# CanController.net
KiCad netlist of a schematic drawn in EAGLE
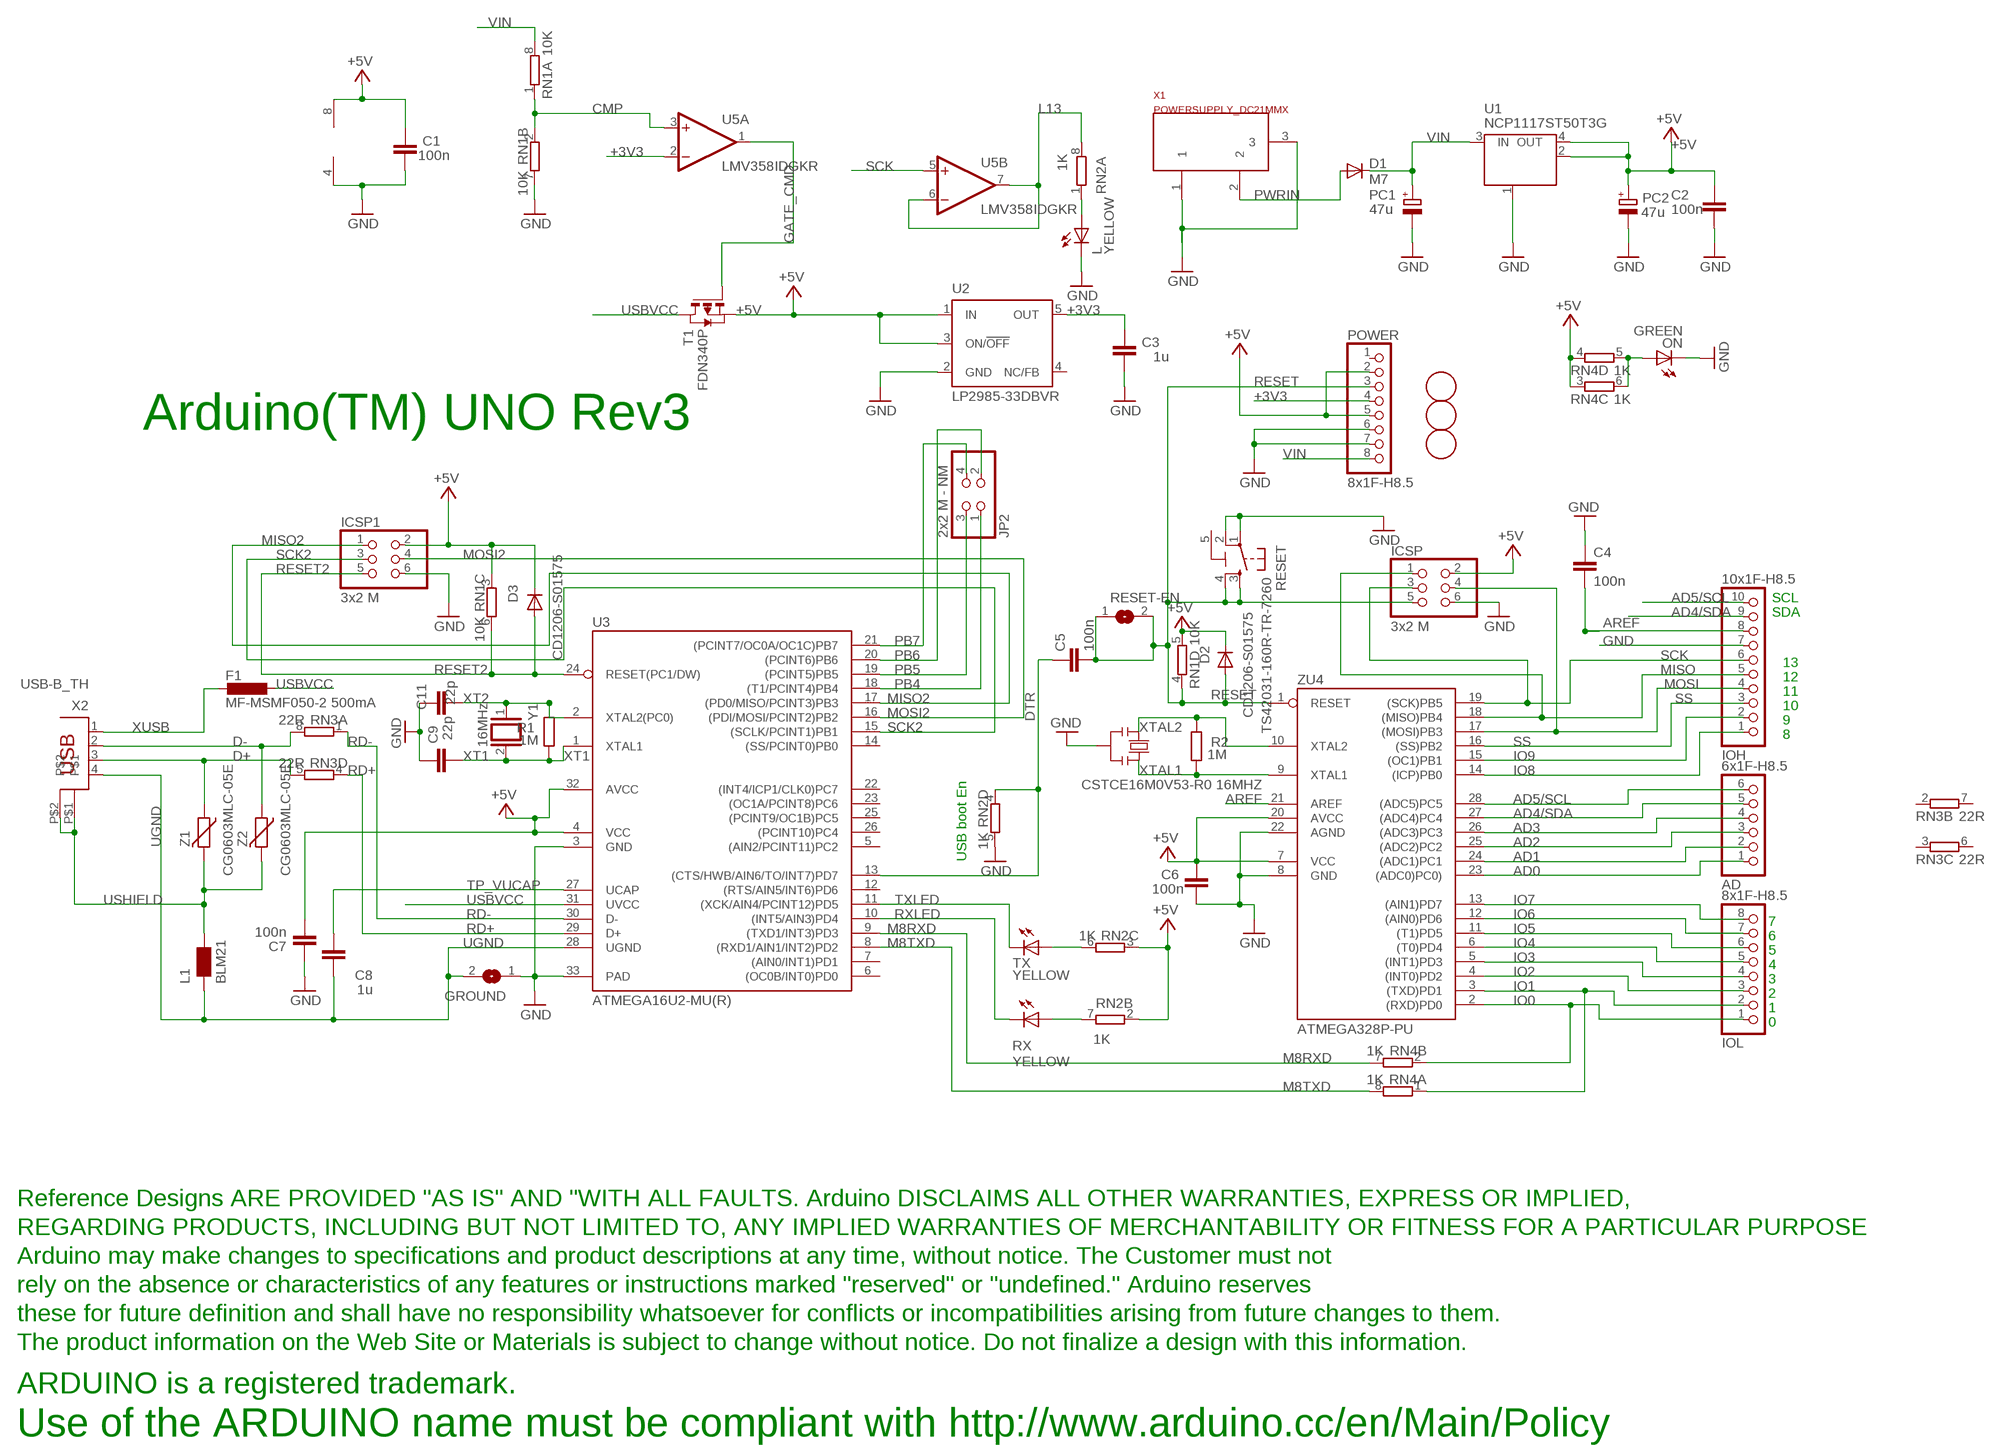
[diagram p0: schematic, sheet 2]

(export (version "E")
  (design (tool "Eeschema 10.0.6"))
  (components
    (comp (ref "AD")
      (value "6x1F-H8.5")
      (footprint "eagle-import:1X06")
      (libsource (lib "eagle-import") (part "PINHD-1X6"))
    )
    (comp (ref "C1")
      (value "100n")
      (footprint "eagle-import:C0603-ROUND")
      (libsource (lib "eagle-import") (part "C-EU0603-RND"))
    )
    (comp (ref "C2")
      (value "100n")
      (footprint "eagle-import:C0603-ROUND")
      (libsource (lib "eagle-import") (part "C-EU0603-RND"))
    )
    (comp (ref "C3")
      (value "1u")
      (footprint "eagle-import:C0603-ROUND")
      (libsource (lib "eagle-import") (part "C-EU0603-RND"))
    )
    (comp (ref "C4")
      (value "100n")
      (footprint "eagle-import:C0603-ROUND")
      (libsource (lib "eagle-import") (part "C-EU0603-RND"))
    )
    (comp (ref "C5")
      (value "100n")
      (footprint "eagle-import:C0603-ROUND")
      (libsource (lib "eagle-import") (part "C-EU0603-RND"))
    )
    (comp (ref "C6")
      (value "100n")
      (footprint "eagle-import:C0603-ROUND")
      (libsource (lib "eagle-import") (part "C-EU0603-RND"))
    )
    (comp (ref "C7")
      (value "100n")
      (footprint "eagle-import:C0603-ROUND")
      (libsource (lib "eagle-import") (part "C-EU0603-RND"))
    )
    (comp (ref "C8")
      (value "1u")
      (footprint "eagle-import:C0603-ROUND")
      (libsource (lib "eagle-import") (part "C-EU0603-RND"))
    )
    (comp (ref "C9")
      (value "22p")
      (footprint "eagle-import:C0603-ROUND")
      (libsource (lib "eagle-import") (part "C-EU0603-RND"))
    )
    (comp (ref "C11")
      (value "22p")
      (footprint "eagle-import:C0603-ROUND")
      (libsource (lib "eagle-import") (part "C-EU0603-RND"))
    )
    (comp (ref "D1")
      (value "M7")
      (footprint "eagle-import:SMB")
      (libsource (lib "eagle-import") (part "DIODE-SMB"))
    )
    (comp (ref "D2")
      (value "CD1206-S01575")
      (footprint "eagle-import:MINIMELF")
      (libsource (lib "eagle-import") (part "DIODE-MINIMELF"))
    )
    (comp (ref "D3")
      (value "CD1206-S01575")
      (footprint "eagle-import:MINIMELF")
      (libsource (lib "eagle-import") (part "DIODE-MINIMELF"))
    )
    (comp (ref "F1")
      (value "MF-MSMF050-2 500mA")
      (footprint "eagle-import:L1812")
      (libsource (lib "eagle-import") (part "L-EUL1812"))
    )
    (comp (ref "FD1")
      (value "FIDUCIALMOUNT")
      (footprint "eagle-import:FIDUCIA-MOUNT")
      (libsource (lib "eagle-import") (part "FIDUCIALMOUNT"))
    )
    (comp (ref "FD2")
      (value "FIDUCIALMOUNT")
      (footprint "eagle-import:FIDUCIA-MOUNT")
      (libsource (lib "eagle-import") (part "FIDUCIALMOUNT"))
    )
    (comp (ref "FD3")
      (value "FIDUCIALMOUNT")
      (footprint "eagle-import:FIDUCIA-MOUNT")
      (libsource (lib "eagle-import") (part "FIDUCIALMOUNT"))
    )
    (comp (ref "GROUND")
      (value "SJ")
      (footprint "eagle-import:SJ")
      (libsource (lib "eagle-import") (part "SJ"))
    )
    (comp (ref "ICSP")
      (value "3x2 M")
      (footprint "eagle-import:2X03")
      (libsource (lib "eagle-import") (part "PINHD-2X3"))
    )
    (comp (ref "ICSP1")
      (value "3x2 M")
      (footprint "eagle-import:2X03")
      (libsource (lib "eagle-import") (part "PINHD-2X3"))
    )
    (comp (ref "IOH")
      (value "10x1F-H8.5")
      (footprint "eagle-import:1X10")
      (libsource (lib "eagle-import") (part "PINHD-1X10_ARD"))
    )
    (comp (ref "IOL")
      (value "8x1F-H8.5")
      (footprint "eagle-import:1X08")
      (libsource (lib "eagle-import") (part "PINHD-1X8"))
    )
    (comp (ref "JP2")
      (value "2x2 M - NM")
      (footprint "eagle-import:2X02")
      (libsource (lib "eagle-import") (part "PINHD-2X2"))
    )
    (comp (ref "L")
      (value "YELLOW")
      (footprint "eagle-import:CHIP-LED0805")
      (libsource (lib "eagle-import") (part "LEDCHIP-LED0805"))
    )
    (comp (ref "L1")
      (value "BLM21")
      (footprint "eagle-import:0805")
      (libsource (lib "eagle-import") (part "WE-CBF_0805"))
    )
    (comp (ref "ON")
      (value "GREEN")
      (footprint "eagle-import:CHIP-LED0805")
      (libsource (lib "eagle-import") (part "LEDCHIP-LED0805"))
    )
    (comp (ref "PC1")
      (value "47u")
      (footprint "eagle-import:PANASONIC_D")
      (libsource (lib "eagle-import") (part "CPOL-EUD"))
    )
    (comp (ref "PC2")
      (value "47u")
      (footprint "eagle-import:PANASONIC_D")
      (libsource (lib "eagle-import") (part "CPOL-EUD"))
    )
    (comp (ref "POWER")
      (value "8x1F-H8.5")
      (footprint "eagle-import:1X08")
      (libsource (lib "eagle-import") (part "PINHD-1X8"))
    )
    (comp (ref "R1")
      (value "1M")
      (footprint "eagle-import:R0603-ROUND")
      (libsource (lib "eagle-import") (part "R-EU_R0603"))
    )
    (comp (ref "R2")
      (value "1M")
      (footprint "eagle-import:R0603-ROUND")
      (libsource (lib "eagle-import") (part "R-EU_R0603"))
    )
    (comp (ref "RESET")
      (value "TS42031-160R-TR-7260")
      (footprint "eagle-import:TS42")
      (libsource (lib "eagle-import") (part "TS42"))
    )
    (comp (ref "RESET-EN")
      (value "SJ")
      (footprint "eagle-import:SJ")
      (libsource (lib "eagle-import") (part "SJ"))
    )
    (comp (ref "RN1")
      (value "10K")
      (footprint "eagle-import:CAY16")
      (libsource (lib "eagle-import") (part "4R-NCAY16"))
    )
    (comp (ref "RN2")
      (value "1K")
      (footprint "eagle-import:CAY16")
      (libsource (lib "eagle-import") (part "4R-NCAY16"))
    )
    (comp (ref "RN3")
      (value "22R")
      (footprint "eagle-import:CAY16")
      (libsource (lib "eagle-import") (part "4R-NCAY16"))
    )
    (comp (ref "RN4")
      (value "1K")
      (footprint "eagle-import:CAY16")
      (libsource (lib "eagle-import") (part "4R-NCAY16"))
    )
    (comp (ref "RX")
      (value "YELLOW")
      (footprint "eagle-import:CHIP-LED0805")
      (libsource (lib "eagle-import") (part "LEDCHIP-LED0805"))
    )
    (comp (ref "T1")
      (value "FDN340P")
      (footprint "eagle-import:SOT-23")
      (libsource (lib "eagle-import") (part "PMOSSOT23"))
    )
    (comp (ref "TX")
      (value "YELLOW")
      (footprint "eagle-import:CHIP-LED0805")
      (libsource (lib "eagle-import") (part "LEDCHIP-LED0805"))
    )
    (comp (ref "U$1")
      (value "DISCLAIMER")
      (footprint "eagle-import:DISCLAIMER")
      (libsource (lib "eagle-import") (part "DISCLAIMER"))
    )
    (comp (ref "U1")
      (value "NCP1117ST50T3G")
      (footprint "eagle-import:SOT223")
      (libsource (lib "eagle-import") (part "MC33269ST-3.3T3"))
    )
    (comp (ref "U2")
      (value "LP2985-33DBVR")
      (footprint "eagle-import:SOT23-DBV")
      (libsource (lib "eagle-import") (part "LP2985-XXDBVR33"))
    )
    (comp (ref "U3")
      (value "ATMEGA16U2-MU(R)")
      (footprint "eagle-import:MLF32")
      (libsource (lib "eagle-import") (part "ATMEGA16U2-MU"))
    )
    (comp (ref "U5")
      (value "LMV358IDGKR")
      (footprint "eagle-import:MSOP08")
      (libsource (lib "eagle-import") (part "LMV358?MMX"))
    )
    (comp (ref "X1")
      (value "POWERSUPPLY_DC21MMX")
      (footprint "eagle-import:POWERSUPPLY_DC-21MM")
      (libsource (lib "eagle-import") (part "POWERSUPPLY_DC21MMX"))
    )
    (comp (ref "X2")
      (value "USB-B_TH")
      (footprint "eagle-import:PN61729")
      (libsource (lib "eagle-import") (part "PN61729"))
    )
    (comp (ref "Y1")
      (value "16MHz")
      (footprint "eagle-import:QS")
      (libsource (lib "eagle-import") (part "XTAL/S"))
    )
    (comp (ref "Y2")
      (value "CSTCE16M0V53-R0 16MHZ")
      (footprint "eagle-import:RESONATOR")
      (libsource (lib "eagle-import") (part "RESONATORMU"))
    )
    (comp (ref "Z1")
      (value "CG0603MLC-05E")
      (footprint "eagle-import:CT_CN0603")
      (libsource (lib "eagle-import") (part "VARISTORCN0603"))
    )
    (comp (ref "Z2")
      (value "CG0603MLC-05E")
      (footprint "eagle-import:CT_CN0603")
      (libsource (lib "eagle-import") (part "VARISTORCN0603"))
    )
    (comp (ref "ZU4")
      (value "ATMEGA328P-PU")
      (footprint "eagle-import:DIL28-3")
      (libsource (lib "eagle-import") (part "ATMEGA328P-PU"))
    )
  )
  (nets
    (net (code "1") (name "+3V3") (class "Default")
      (node (ref "C3") (pin "2") (pinfunction "2_2") (pintype "passive"))
      (node (ref "POWER") (pin "4") (pinfunction "4_4") (pintype "passive"))
      (node (ref "U2") (pin "5") (pinfunction "OUT_5") (pintype "passive"))
      (node (ref "U5") (pin "2") (pinfunction "-IN_2") (pintype "input"))
    )
    (net (code "2") (name "+5V") (class "Default")
      (node (ref "C1") (pin "2") (pinfunction "2_2") (pintype "passive"))
      (node (ref "C2") (pin "2") (pinfunction "2_2") (pintype "passive"))
      (node (ref "C6") (pin "2") (pinfunction "2_2") (pintype "passive"))
      (node (ref "C7") (pin "1") (pinfunction "1_1") (pintype "passive"))
      (node (ref "D2") (pin "C") (pinfunction "C_C") (pintype "passive"))
      (node (ref "D3") (pin "C") (pinfunction "C_C") (pintype "passive"))
      (node (ref "ICSP") (pin "2") (pinfunction "2_2") (pintype "passive"))
      (node (ref "ICSP1") (pin "2") (pinfunction "2_2") (pintype "passive"))
      (node (ref "PC2") (pin "+") (pinfunction "+_+") (pintype "passive"))
      (node (ref "POWER") (pin "2") (pinfunction "2_2") (pintype "passive"))
      (node (ref "POWER") (pin "5") (pinfunction "5_5") (pintype "passive"))
      (node (ref "RN1") (pin "3") (pinfunction "1_3") (pintype "passive"))
      (node (ref "RN1") (pin "5") (pinfunction "2_5") (pintype "passive"))
      (node (ref "RN2") (pin "2") (pinfunction "1_2") (pintype "passive"))
      (node (ref "RN2") (pin "3") (pinfunction "1_3") (pintype "passive"))
      (node (ref "RN4") (pin "3") (pinfunction "1_3") (pintype "passive"))
      (node (ref "RN4") (pin "4") (pinfunction "1_4") (pintype "passive"))
      (node (ref "T1") (pin "2") (pinfunction "S_2") (pintype "passive"))
      (node (ref "U1") (pin "2") (pinfunction "OUT_2") (pintype "passive"))
      (node (ref "U1") (pin "4") (pinfunction "OUT_4") (pintype "passive"))
      (node (ref "U2") (pin "1") (pinfunction "IN_1") (pintype "input"))
      (node (ref "U2") (pin "3") (pinfunction "ON/~{OFF}_3") (pintype "input"))
      (node (ref "U3") (pin "32") (pinfunction "AVCC_32") (pintype "power_in"))
      (node (ref "U3") (pin "4") (pinfunction "VCC_4") (pintype "power_in"))
      (node (ref "U5") (pin "8") (pinfunction "V+_8") (pintype "power_in"))
      (node (ref "ZU4") (pin "20") (pinfunction "AVCC_20") (pintype "power_in"))
      (node (ref "ZU4") (pin "7") (pinfunction "VCC_7") (pintype "power_in"))
    )
    (net (code "3") (name "5-GND") (class "Default")
      (node (ref "RESET") (pin "5") (pinfunction "5-GND_5") (pintype "power_in"))
    )
    (net (code "4") (name "AD0") (class "Default")
      (node (ref "AD") (pin "1") (pinfunction "1_1") (pintype "passive"))
      (node (ref "ZU4") (pin "23") (pinfunction "(ADC0)PC0)_23") (pintype "bidirectional"))
    )
    (net (code "5") (name "AD1") (class "Default")
      (node (ref "AD") (pin "2") (pinfunction "2_2") (pintype "passive"))
      (node (ref "ZU4") (pin "24") (pinfunction "(ADC1)PC1_24") (pintype "bidirectional"))
    )
    (net (code "6") (name "AD2") (class "Default")
      (node (ref "AD") (pin "3") (pinfunction "3_3") (pintype "passive"))
      (node (ref "ZU4") (pin "25") (pinfunction "(ADC2)PC2_25") (pintype "bidirectional"))
    )
    (net (code "7") (name "AD3") (class "Default")
      (node (ref "AD") (pin "4") (pinfunction "4_4") (pintype "passive"))
      (node (ref "ZU4") (pin "26") (pinfunction "(ADC3)PC3_26") (pintype "bidirectional"))
    )
    (net (code "8") (name "AD4{slash}SDA") (class "Default")
      (node (ref "AD") (pin "5") (pinfunction "5_5") (pintype "passive"))
      (node (ref "IOH") (pin "9") (pinfunction "9_9") (pintype "passive"))
      (node (ref "ZU4") (pin "27") (pinfunction "(ADC4)PC4_27") (pintype "bidirectional"))
    )
    (net (code "9") (name "AD5{slash}SCL") (class "Default")
      (node (ref "AD") (pin "6") (pinfunction "6_6") (pintype "passive"))
      (node (ref "IOH") (pin "10") (pinfunction "10_10") (pintype "passive"))
      (node (ref "ZU4") (pin "28") (pinfunction "(ADC5)PC5_28") (pintype "bidirectional"))
    )
    (net (code "10") (name "AREF") (class "Default")
      (node (ref "C4") (pin "2") (pinfunction "2_2") (pintype "passive"))
      (node (ref "IOH") (pin "8") (pinfunction "8_8") (pintype "passive"))
      (node (ref "ZU4") (pin "21") (pinfunction "AREF_21") (pintype "passive"))
    )
    (net (code "11") (name "CMP") (class "Default")
      (node (ref "RN1") (pin "1") (pinfunction "1_1") (pintype "passive"))
      (node (ref "RN1") (pin "2") (pinfunction "1_2") (pintype "passive"))
      (node (ref "U5") (pin "3") (pinfunction "+IN_3") (pintype "input"))
    )
    (net (code "12") (name "D+") (class "Default")
      (node (ref "RN3") (pin "5") (pinfunction "2_5") (pintype "passive"))
      (node (ref "X2") (pin "3") (pinfunction "3_3") (pintype "bidirectional"))
      (node (ref "Z1") (pin "1") (pinfunction "1_1") (pintype "passive"))
    )
    (net (code "13") (name "D-") (class "Default")
      (node (ref "RN3") (pin "8") (pinfunction "2_8") (pintype "passive"))
      (node (ref "X2") (pin "2") (pinfunction "2_2") (pintype "bidirectional"))
      (node (ref "Z2") (pin "1") (pinfunction "1_1") (pintype "passive"))
    )
    (net (code "14") (name "DTR") (class "Default")
      (node (ref "C5") (pin "1") (pinfunction "1_1") (pintype "passive"))
      (node (ref "RN2") (pin "4") (pinfunction "1_4") (pintype "passive"))
      (node (ref "U3") (pin "13") (pinfunction "(CTS/HWB/AIN6/TO/INT7)PD7_13") (pintype "bidirectional"))
    )
    (net (code "15") (name "GATE_CMD") (class "Default")
      (node (ref "T1") (pin "3") (pinfunction "G_3") (pintype "passive"))
      (node (ref "U5") (pin "1") (pinfunction "OUT_1") (pintype "output"))
    )
    (net (code "16") (name "GND") (class "Default")
      (node (ref "C1") (pin "1") (pinfunction "1_1") (pintype "passive"))
      (node (ref "C11") (pin "2") (pinfunction "2_2") (pintype "passive"))
      (node (ref "C2") (pin "1") (pinfunction "1_1") (pintype "passive"))
      (node (ref "C3") (pin "1") (pinfunction "1_1") (pintype "passive"))
      (node (ref "C4") (pin "1") (pinfunction "1_1") (pintype "passive"))
      (node (ref "C6") (pin "1") (pinfunction "1_1") (pintype "passive"))
      (node (ref "C7") (pin "2") (pinfunction "2_2") (pintype "passive"))
      (node (ref "C9") (pin "2") (pinfunction "2_2") (pintype "passive"))
      (node (ref "GROUND") (pin "1") (pinfunction "1_1") (pintype "passive"))
      (node (ref "ICSP") (pin "6") (pinfunction "6_6") (pintype "passive"))
      (node (ref "ICSP1") (pin "6") (pinfunction "6_6") (pintype "passive"))
      (node (ref "IOH") (pin "7") (pinfunction "7_7") (pintype "passive"))
      (node (ref "L") (pin "C") (pinfunction "C_C") (pintype "passive"))
      (node (ref "ON") (pin "C") (pinfunction "C_C") (pintype "passive"))
      (node (ref "PC1") (pin "-") (pinfunction "-_-") (pintype "passive"))
      (node (ref "PC2") (pin "-") (pinfunction "-_-") (pintype "passive"))
      (node (ref "POWER") (pin "6") (pinfunction "6_6") (pintype "passive"))
      (node (ref "POWER") (pin "7") (pinfunction "7_7") (pintype "passive"))
      (node (ref "RESET") (pin "1") (pinfunction "1_1") (pintype "passive"))
      (node (ref "RESET") (pin "2") (pinfunction "2_2") (pintype "passive"))
      (node (ref "RN1") (pin "7") (pinfunction "2_7") (pintype "passive"))
      (node (ref "RN2") (pin "5") (pinfunction "2_5") (pintype "passive"))
      (node (ref "U1") (pin "1") (pinfunction "GND/ADJ_1") (pintype "input"))
      (node (ref "U2") (pin "2") (pinfunction "GND_2") (pintype "power_in"))
      (node (ref "U3") (pin "3") (pinfunction "GND_3") (pintype "power_in"))
      (node (ref "U3") (pin "33") (pinfunction "PAD_33") (pintype "power_in"))
      (node (ref "U5") (pin "4") (pinfunction "V-_4") (pintype "power_in"))
      (node (ref "X1") (pin "1") (pinfunction "1_1") (pintype "power_in"))
      (node (ref "X1") (pin "3") (pinfunction "3_3") (pintype "power_in"))
      (node (ref "Y2") (pin "2") (pinfunction "2_2") (pintype "passive"))
      (node (ref "ZU4") (pin "22") (pinfunction "AGND_22") (pintype "power_in"))
      (node (ref "ZU4") (pin "8") (pinfunction "GND_8") (pintype "power_in"))
    )
    (net (code "17") (name "IO0") (class "Default")
      (node (ref "IOL") (pin "1") (pinfunction "1_1") (pintype "passive"))
      (node (ref "RN4") (pin "2") (pinfunction "1_2") (pintype "passive"))
      (node (ref "ZU4") (pin "2") (pinfunction "(RXD)PD0_2") (pintype "bidirectional"))
    )
    (net (code "18") (name "IO1") (class "Default")
      (node (ref "IOL") (pin "2") (pinfunction "2_2") (pintype "passive"))
      (node (ref "RN4") (pin "1") (pinfunction "1_1") (pintype "passive"))
      (node (ref "ZU4") (pin "3") (pinfunction "(TXD)PD1_3") (pintype "bidirectional"))
    )
    (net (code "19") (name "IO2") (class "Default")
      (node (ref "IOL") (pin "3") (pinfunction "3_3") (pintype "passive"))
      (node (ref "ZU4") (pin "4") (pinfunction "(INT0)PD2_4") (pintype "bidirectional"))
    )
    (net (code "20") (name "IO3") (class "Default")
      (node (ref "IOL") (pin "4") (pinfunction "4_4") (pintype "passive"))
      (node (ref "ZU4") (pin "5") (pinfunction "(INT1)PD3_5") (pintype "bidirectional"))
    )
    (net (code "21") (name "IO4") (class "Default")
      (node (ref "IOL") (pin "5") (pinfunction "5_5") (pintype "passive"))
      (node (ref "ZU4") (pin "6") (pinfunction "(T0)PD4_6") (pintype "bidirectional"))
    )
    (net (code "22") (name "IO5") (class "Default")
      (node (ref "IOL") (pin "6") (pinfunction "6_6") (pintype "passive"))
      (node (ref "ZU4") (pin "11") (pinfunction "(T1)PD5_11") (pintype "bidirectional"))
    )
    (net (code "23") (name "IO6") (class "Default")
      (node (ref "IOL") (pin "7") (pinfunction "7_7") (pintype "passive"))
      (node (ref "ZU4") (pin "12") (pinfunction "(AIN0)PD6_12") (pintype "bidirectional"))
    )
    (net (code "24") (name "IO7") (class "Default")
      (node (ref "IOL") (pin "8") (pinfunction "8_8") (pintype "passive"))
      (node (ref "ZU4") (pin "13") (pinfunction "(AIN1)PD7_13") (pintype "bidirectional"))
    )
    (net (code "25") (name "IO8") (class "Default")
      (node (ref "IOH") (pin "1") (pinfunction "1_1") (pintype "passive"))
      (node (ref "ZU4") (pin "14") (pinfunction "(ICP)PB0_14") (pintype "bidirectional"))
    )
    (net (code "26") (name "IO9") (class "Default")
      (node (ref "IOH") (pin "2") (pinfunction "2_2") (pintype "passive"))
      (node (ref "ZU4") (pin "15") (pinfunction "(OC1)PB1_15") (pintype "bidirectional"))
    )
    (net (code "27") (name "L13") (class "Default")
      (node (ref "RN2") (pin "8") (pinfunction "2_8") (pintype "passive"))
      (node (ref "U5") (pin "6") (pinfunction "-IN_6") (pintype "input"))
      (node (ref "U5") (pin "7") (pinfunction "OUT_7") (pintype "output"))
    )
    (net (code "28") (name "M8RXD") (class "Default")
      (node (ref "RN4") (pin "7") (pinfunction "2_7") (pintype "passive"))
      (node (ref "U3") (pin "9") (pinfunction "(TXD1/INT3)PD3_9") (pintype "bidirectional"))
    )
    (net (code "29") (name "M8TXD") (class "Default")
      (node (ref "RN4") (pin "8") (pinfunction "2_8") (pintype "passive"))
      (node (ref "U3") (pin "8") (pinfunction "(RXD1/AIN1/INT2)PD2_8") (pintype "bidirectional"))
    )
    (net (code "30") (name "MISO") (class "Default")
      (node (ref "ICSP") (pin "1") (pinfunction "1_1") (pintype "passive"))
      (node (ref "IOH") (pin "5") (pinfunction "5_5") (pintype "passive"))
      (node (ref "ZU4") (pin "18") (pinfunction "(MISO)PB4_18") (pintype "bidirectional"))
    )
    (net (code "31") (name "MISO2") (class "Default")
      (node (ref "ICSP1") (pin "1") (pinfunction "1_1") (pintype "passive"))
      (node (ref "U3") (pin "17") (pinfunction "(PD0/MISO/PCINT3)PB3_17") (pintype "bidirectional"))
    )
    (net (code "32") (name "MOSI") (class "Default")
      (node (ref "ICSP") (pin "4") (pinfunction "4_4") (pintype "passive"))
      (node (ref "IOH") (pin "4") (pinfunction "4_4") (pintype "passive"))
      (node (ref "ZU4") (pin "17") (pinfunction "(MOSI)PB3_17") (pintype "bidirectional"))
    )
    (net (code "33") (name "MOSI2") (class "Default")
      (node (ref "ICSP1") (pin "4") (pinfunction "4_4") (pintype "passive"))
      (node (ref "U3") (pin "16") (pinfunction "(PDI/MOSI/PCINT2)PB2_16") (pintype "bidirectional"))
    )
    (net (code "34") (name "Net-(L-PadA)") (class "Default")
      (node (ref "L") (pin "A") (pinfunction "A_A") (pintype "passive"))
      (node (ref "RN2") (pin "1") (pinfunction "1_1") (pintype "passive"))
    )
    (net (code "35") (name "Net-(RN2B-2)") (class "Default")
      (node (ref "RN2") (pin "7") (pinfunction "2_7") (pintype "passive"))
      (node (ref "RX") (pin "A") (pinfunction "A_A") (pintype "passive"))
    )
    (net (code "36") (name "Net-(RN2C-2)") (class "Default")
      (node (ref "RN2") (pin "6") (pinfunction "2_6") (pintype "passive"))
      (node (ref "TX") (pin "A") (pinfunction "A_A") (pintype "passive"))
    )
    (net (code "37") (name "Net-(RN4C-2)") (class "Default")
      (node (ref "ON") (pin "A") (pinfunction "A_A") (pintype "passive"))
      (node (ref "RN4") (pin "5") (pinfunction "2_5") (pintype "passive"))
      (node (ref "RN4") (pin "6") (pinfunction "2_6") (pintype "passive"))
    )
    (net (code "38") (name "PB4") (class "Default")
      (node (ref "JP2") (pin "1") (pinfunction "1_1") (pintype "passive"))
      (node (ref "U3") (pin "18") (pinfunction "(T1/PCINT4)PB4_18") (pintype "bidirectional"))
    )
    (net (code "39") (name "PB5") (class "Default")
      (node (ref "JP2") (pin "3") (pinfunction "3_3") (pintype "passive"))
      (node (ref "U3") (pin "19") (pinfunction "(PCINT5)PB5_19") (pintype "bidirectional"))
    )
    (net (code "40") (name "PB6") (class "Default")
      (node (ref "JP2") (pin "2") (pinfunction "2_2") (pintype "passive"))
      (node (ref "U3") (pin "20") (pinfunction "(PCINT6)PB6_20") (pintype "bidirectional"))
    )
    (net (code "41") (name "PB7") (class "Default")
      (node (ref "JP2") (pin "4") (pinfunction "4_4") (pintype "passive"))
      (node (ref "U3") (pin "21") (pinfunction "(PCINT7/OC0A/OC1C)PB7_21") (pintype "bidirectional"))
    )
    (net (code "42") (name "PWRIN") (class "Default")
      (node (ref "D1") (pin "A") (pinfunction "A_A") (pintype "passive"))
      (node (ref "X1") (pin "2") (pinfunction "2_2") (pintype "power_in"))
    )
    (net (code "43") (name "RD+") (class "Default")
      (node (ref "RN3") (pin "4") (pinfunction "1_4") (pintype "passive"))
      (node (ref "U3") (pin "29") (pinfunction "D+_29") (pintype "bidirectional"))
    )
    (net (code "44") (name "RD-") (class "Default")
      (node (ref "RN3") (pin "1") (pinfunction "1_1") (pintype "passive"))
      (node (ref "U3") (pin "30") (pinfunction "D-_30") (pintype "bidirectional"))
    )
    (net (code "45") (name "RESET") (class "Default")
      (node (ref "C5") (pin "2") (pinfunction "2_2") (pintype "passive"))
      (node (ref "D2") (pin "A") (pinfunction "A_A") (pintype "passive"))
      (node (ref "ICSP") (pin "5") (pinfunction "5_5") (pintype "passive"))
      (node (ref "POWER") (pin "3") (pinfunction "3_3") (pintype "passive"))
      (node (ref "RESET") (pin "3") (pinfunction "3_3") (pintype "passive"))
      (node (ref "RESET") (pin "4") (pinfunction "4_4") (pintype "passive"))
      (node (ref "RESET-EN") (pin "1") (pinfunction "1_1") (pintype "passive"))
      (node (ref "RESET-EN") (pin "2") (pinfunction "2_2") (pintype "passive"))
      (node (ref "RN1") (pin "4") (pinfunction "1_4") (pintype "passive"))
      (node (ref "ZU4") (pin "1") (pinfunction "RESET_1") (pintype "input"))
    )
    (net (code "46") (name "RESET2") (class "Default")
      (node (ref "D3") (pin "A") (pinfunction "A_A") (pintype "passive"))
      (node (ref "ICSP1") (pin "5") (pinfunction "5_5") (pintype "passive"))
      (node (ref "RN1") (pin "6") (pinfunction "2_6") (pintype "passive"))
      (node (ref "U3") (pin "24") (pinfunction "RESET(PC1/DW)_24") (pintype "input"))
    )
    (net (code "47") (name "RXLED") (class "Default")
      (node (ref "RX") (pin "C") (pinfunction "C_C") (pintype "passive"))
      (node (ref "U3") (pin "10") (pinfunction "(INT5/AIN3)PD4_10") (pintype "bidirectional"))
    )
    (net (code "48") (name "SCK") (class "Default")
      (node (ref "ICSP") (pin "3") (pinfunction "3_3") (pintype "passive"))
      (node (ref "IOH") (pin "6") (pinfunction "6_6") (pintype "passive"))
      (node (ref "U5") (pin "5") (pinfunction "+IN_5") (pintype "input"))
      (node (ref "ZU4") (pin "19") (pinfunction "(SCK)PB5_19") (pintype "bidirectional"))
    )
    (net (code "49") (name "SCK2") (class "Default")
      (node (ref "ICSP1") (pin "3") (pinfunction "3_3") (pintype "passive"))
      (node (ref "U3") (pin "15") (pinfunction "(SCLK/PCINT1)PB1_15") (pintype "bidirectional"))
    )
    (net (code "50") (name "SS") (class "Default")
      (node (ref "IOH") (pin "3") (pinfunction "3_3") (pintype "passive"))
      (node (ref "ZU4") (pin "16") (pinfunction "(SS)PB2_16") (pintype "bidirectional"))
    )
    (net (code "51") (name "TP_VUCAP") (class "Default")
      (node (ref "C8") (pin "1") (pinfunction "1_1") (pintype "passive"))
      (node (ref "U3") (pin "27") (pinfunction "UCAP_27") (pintype "passive"))
    )
    (net (code "52") (name "TXLED") (class "Default")
      (node (ref "TX") (pin "C") (pinfunction "C_C") (pintype "passive"))
      (node (ref "U3") (pin "11") (pinfunction "(XCK/AIN4/PCINT12)PD5_11") (pintype "bidirectional"))
    )
    (net (code "53") (name "UGND") (class "Default")
      (node (ref "C8") (pin "2") (pinfunction "2_2") (pintype "passive"))
      (node (ref "GROUND") (pin "2") (pinfunction "2_2") (pintype "passive"))
      (node (ref "L1") (pin "1") (pinfunction "1_1") (pintype "passive"))
      (node (ref "U3") (pin "28") (pinfunction "UGND_28") (pintype "power_in"))
      (node (ref "X2") (pin "4") (pinfunction "4_4") (pintype "bidirectional"))
    )
    (net (code "54") (name "USBVCC") (class "Default")
      (node (ref "F1") (pin "1") (pinfunction "1_1") (pintype "passive"))
      (node (ref "T1") (pin "1") (pinfunction "D_1") (pintype "passive"))
      (node (ref "U3") (pin "31") (pinfunction "UVCC_31") (pintype "power_in"))
    )
    (net (code "55") (name "USHIELD") (class "Default")
      (node (ref "L1") (pin "2") (pinfunction "2_2") (pintype "passive"))
      (node (ref "X2") (pin "P$1") (pinfunction "P$1_P$1") (pintype "bidirectional"))
      (node (ref "X2") (pin "P$2") (pinfunction "P$2_P$2") (pintype "bidirectional"))
      (node (ref "Z1") (pin "2") (pinfunction "2_2") (pintype "passive"))
      (node (ref "Z2") (pin "2") (pinfunction "2_2") (pintype "passive"))
    )
    (net (code "56") (name "VIN") (class "Default")
      (node (ref "D1") (pin "C") (pinfunction "C_C") (pintype "passive"))
      (node (ref "PC1") (pin "+") (pinfunction "+_+") (pintype "passive"))
      (node (ref "POWER") (pin "8") (pinfunction "8_8") (pintype "passive"))
      (node (ref "RN1") (pin "8") (pinfunction "2_8") (pintype "passive"))
      (node (ref "U1") (pin "3") (pinfunction "IN_3") (pintype "input"))
    )
    (net (code "57") (name "XT1") (class "Default")
      (node (ref "C9") (pin "1") (pinfunction "1_1") (pintype "passive"))
      (node (ref "R1") (pin "1") (pinfunction "1_1") (pintype "passive"))
      (node (ref "U3") (pin "1") (pinfunction "XTAL1_1") (pintype "bidirectional"))
      (node (ref "Y1") (pin "2") (pinfunction "2_2") (pintype "passive"))
    )
    (net (code "58") (name "XT2") (class "Default")
      (node (ref "C11") (pin "1") (pinfunction "1_1") (pintype "passive"))
      (node (ref "R1") (pin "2") (pinfunction "2_2") (pintype "passive"))
      (node (ref "U3") (pin "2") (pinfunction "XTAL2(PC0)_2") (pintype "bidirectional"))
      (node (ref "Y1") (pin "1") (pinfunction "1_1") (pintype "passive"))
    )
    (net (code "59") (name "XTAL1") (class "Default")
      (node (ref "R2") (pin "1") (pinfunction "1_1") (pintype "passive"))
      (node (ref "Y2") (pin "3") (pinfunction "3_3") (pintype "passive"))
      (node (ref "ZU4") (pin "9") (pinfunction "XTAL1_9") (pintype "bidirectional"))
    )
    (net (code "60") (name "XTAL2") (class "Default")
      (node (ref "R2") (pin "2") (pinfunction "2_2") (pintype "passive"))
      (node (ref "Y2") (pin "1") (pinfunction "1_1") (pintype "passive"))
      (node (ref "ZU4") (pin "10") (pinfunction "XTAL2_10") (pintype "bidirectional"))
    )
    (net (code "61") (name "XUSB") (class "Default")
      (node (ref "F1") (pin "2") (pinfunction "2_2") (pintype "passive"))
      (node (ref "X2") (pin "1") (pinfunction "1_1") (pintype "bidirectional"))
    )
    (net (code "62") (name "unconnected-(POWER-Pad1)") (class "Default")
      (node (ref "POWER") (pin "1") (pinfunction "1_1") (pintype "passive"))
    )
    (net (code "63") (name "unconnected-(RN3B-1-Pad2)") (class "Default")
      (node (ref "RN3") (pin "2") (pinfunction "1_2") (pintype "passive"))
    )
    (net (code "64") (name "unconnected-(RN3B-2-Pad7)") (class "Default")
      (node (ref "RN3") (pin "7") (pinfunction "2_7") (pintype "passive"))
    )
    (net (code "65") (name "unconnected-(RN3C-1-Pad3)") (class "Default")
      (node (ref "RN3") (pin "3") (pinfunction "1_3") (pintype "passive"))
    )
    (net (code "66") (name "unconnected-(RN3C-2-Pad6)") (class "Default")
      (node (ref "RN3") (pin "6") (pinfunction "2_6") (pintype "passive"))
    )
    (net (code "67") (name "unconnected-(U2-NC{slash}FB-Pad4)") (class "Default")
      (node (ref "U2") (pin "4") (pinfunction "NC/FB_4") (pintype "passive"))
    )
    (net (code "68") (name "unconnected-(U3-(AIN0{slash}INT1)PD1-Pad7)") (class "Default")
      (node (ref "U3") (pin "7") (pinfunction "(AIN0/INT1)PD1_7") (pintype "bidirectional"))
    )
    (net (code "69") (name "unconnected-(U3-(AIN2{slash}PCINT11)PC2-Pad5)") (class "Default")
      (node (ref "U3") (pin "5") (pinfunction "(AIN2/PCINT11)PC2_5") (pintype "bidirectional"))
    )
    (net (code "70") (name "unconnected-(U3-(INT4{slash}ICP1{slash}CLK0)PC7-Pad22)") (class "Default")
      (node (ref "U3") (pin "22") (pinfunction "(INT4/ICP1/CLK0)PC7_22") (pintype "bidirectional"))
    )
    (net (code "71") (name "unconnected-(U3-(OC0B{slash}INT0)PD0-Pad6)") (class "Default")
      (node (ref "U3") (pin "6") (pinfunction "(OC0B/INT0)PD0_6") (pintype "bidirectional"))
    )
    (net (code "72") (name "unconnected-(U3-(OC1A{slash}PCINT8)PC6-Pad23)") (class "Default")
      (node (ref "U3") (pin "23") (pinfunction "(OC1A/PCINT8)PC6_23") (pintype "bidirectional"))
    )
    (net (code "73") (name "unconnected-(U3-(PCINT9{slash}OC1B)PC5-Pad25)") (class "Default")
      (node (ref "U3") (pin "25") (pinfunction "(PCINT9/OC1B)PC5_25") (pintype "bidirectional"))
    )
    (net (code "74") (name "unconnected-(U3-(PCINT10)PC4-Pad26)") (class "Default")
      (node (ref "U3") (pin "26") (pinfunction "(PCINT10)PC4_26") (pintype "bidirectional"))
    )
    (net (code "75") (name "unconnected-(U3-(RTS{slash}AIN5{slash}INT6)PD6-Pad12)") (class "Default")
      (node (ref "U3") (pin "12") (pinfunction "(RTS/AIN5/INT6)PD6_12") (pintype "bidirectional"))
    )
    (net (code "76") (name "unconnected-(U3-(SS{slash}PCINT0)PB0-Pad14)") (class "Default")
      (node (ref "U3") (pin "14") (pinfunction "(SS/PCINT0)PB0_14") (pintype "bidirectional"))
    )
  )
)
